# linear_DC_voltage_reg.net
KiCad netlist of a schematic drawn in EAGLE
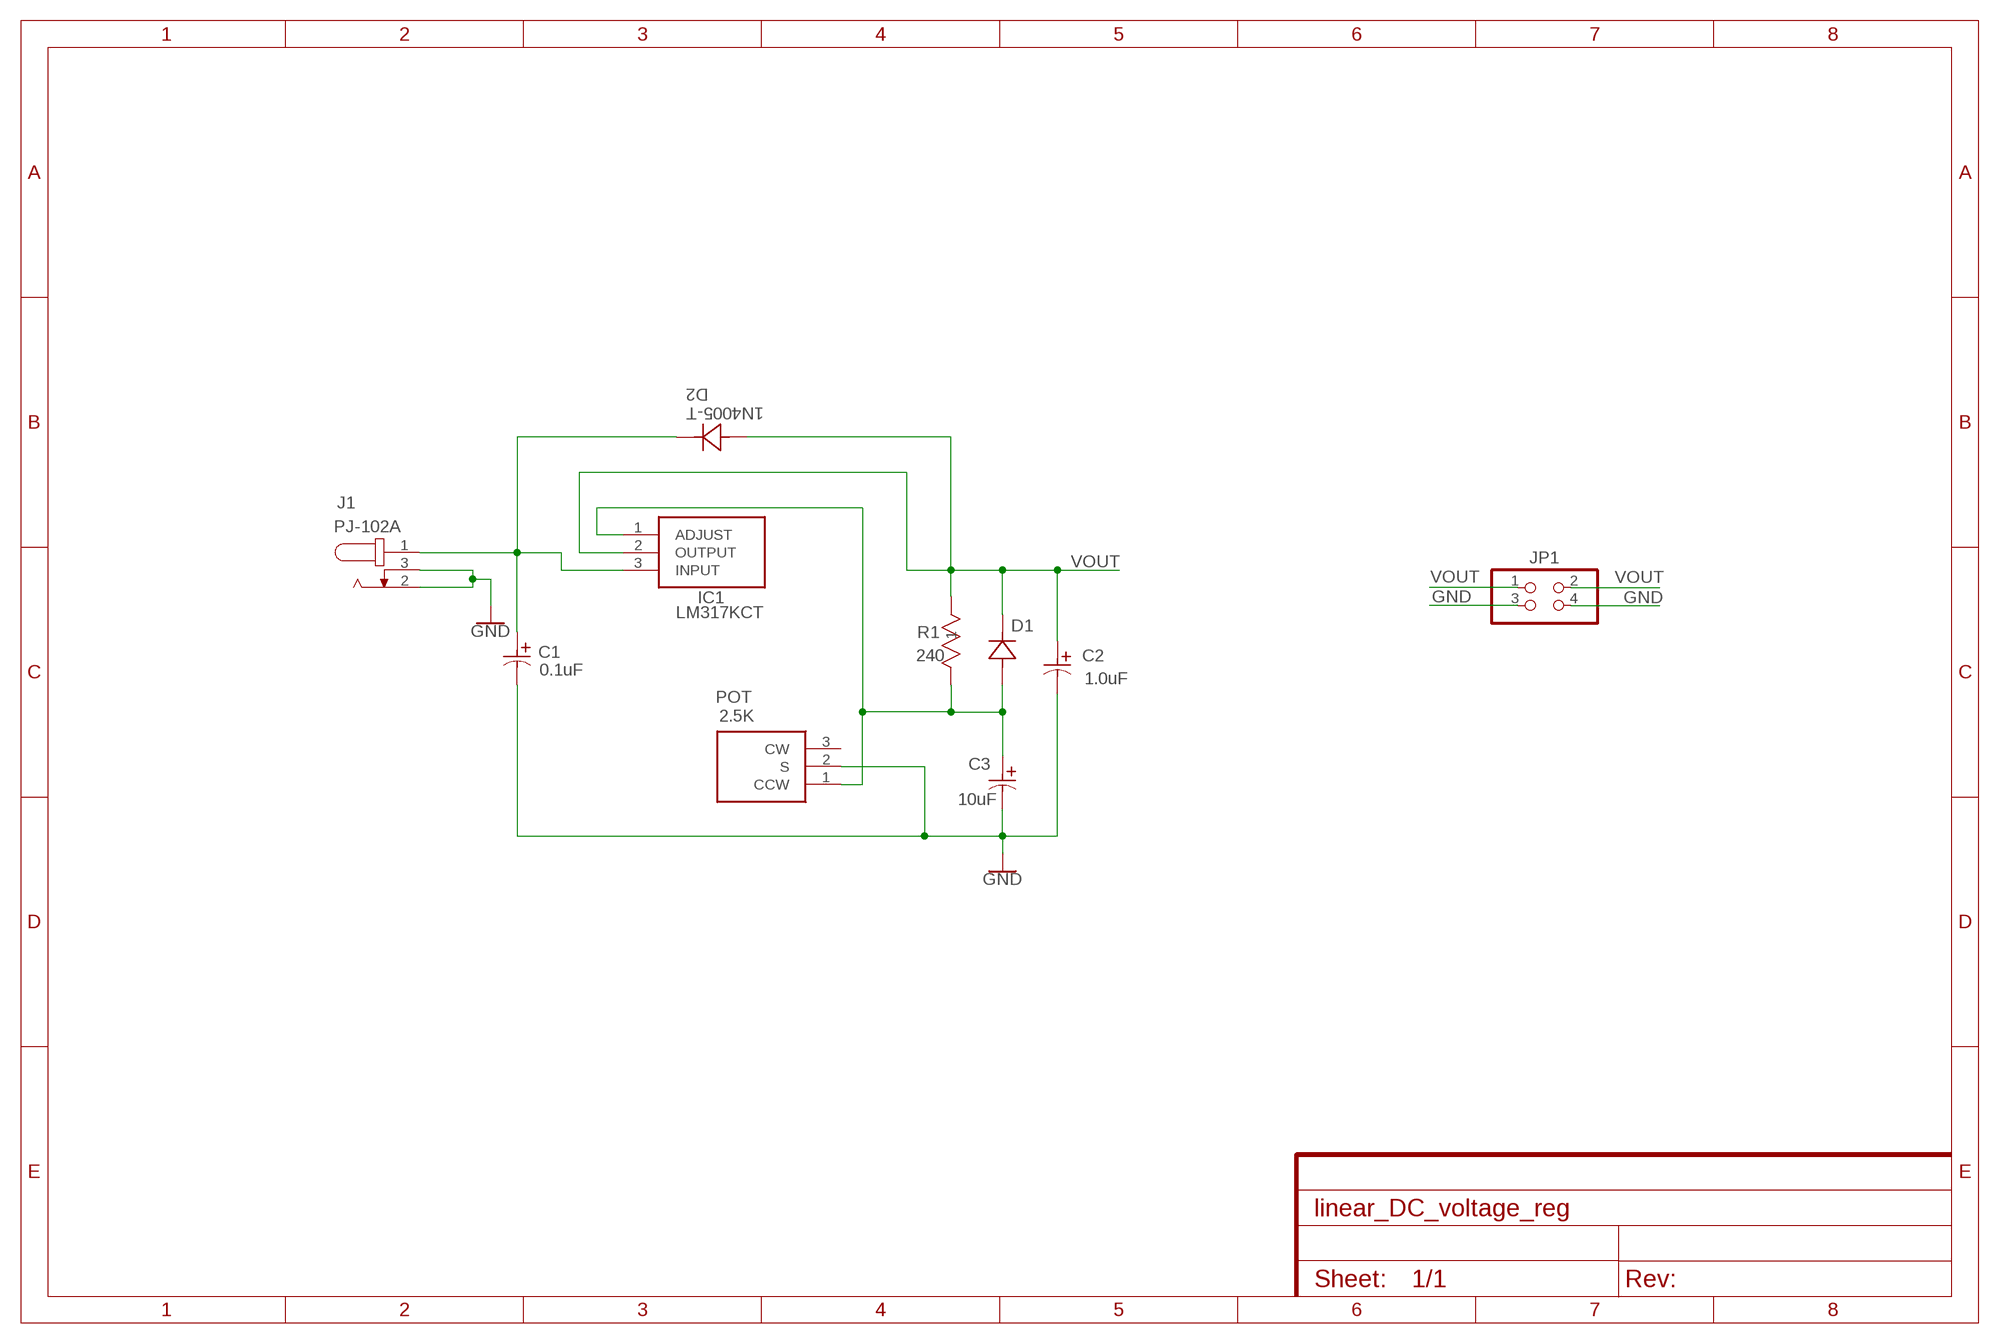
[diagram p0: schematic, sheet 1]

(export (version "E")
  (design (tool "Eeschema 10.0.6"))
  (components
    (comp (ref "C1")
      (value "0.1uF")
      (footprint "eagle-import:CAP_C322_KEM")
      (fields
        (field (name "MANUFACTURER_PART_NUMBER") "C322C104K5R5TA")
        (field (name "COPYRIGHT") "Copyright (C) 2021 Ultra Librarian. All rights reserved.")
      )
      (libsource (lib "eagle-import") (part "C322C104K5R5TA"))
    )
    (comp (ref "C2")
      (value "1.0uF")
      (footprint "eagle-import:CAP_C322_KEM")
      (fields
        (field (name "MANUFACTURER_PART_NUMBER") "C322C104K5R5TA")
        (field (name "COPYRIGHT") "Copyright (C) 2021 Ultra Librarian. All rights reserved.")
      )
      (libsource (lib "eagle-import") (part "C322C104K5R5TA"))
    )
    (comp (ref "C3")
      (value "10uF")
      (footprint "eagle-import:CAP_C322_KEM")
      (fields
        (field (name "MANUFACTURER_PART_NUMBER") "C322C104K5R5TA")
        (field (name "COPYRIGHT") "Copyright (C) 2021 Ultra Librarian. All rights reserved.")
      )
      (libsource (lib "eagle-import") (part "C322C104K5R5TA"))
    )
    (comp (ref "D1")
      (value "1N4005-T")
      (footprint "eagle-import:DO-41_DIO")
      (fields (field (name "COPYRIGHT") "Copyright (C) 2021 Ultra Librarian. All rights reserved."))
      (libsource (lib "eagle-import") (part "1N4005-T"))
    )
    (comp (ref "D2")
      (value "1N4005-T")
      (footprint "eagle-import:DO-41_DIO")
      (fields (field (name "COPYRIGHT") "Copyright (C) 2021 Ultra Librarian. All rights reserved."))
      (libsource (lib "eagle-import") (part "1N4005-T"))
    )
    (comp (ref "IC1")
      (value "LM317KCT")
      (footprint "eagle-import:TO254P465X1016X1883-3P")
      (fields (field (name "MOUSER_PART_NUMBER") "595-LM317KCT"))
      (libsource (lib "eagle-import") (part "LM317KCT"))
    )
    (comp (ref "J1")
      (value "PJ-102A")
      (footprint "eagle-import:CUI_PJ-102A")
      (fields (field (name "DIGI-KEY_PART_NUMBER") "CP-102AH-ND") (field (name "MF") "CUI Devices"))
      (libsource (lib "eagle-import") (part "PJ-102A"))
    )
    (comp (ref "JP1")
      (value "PINHD-2X2")
      (footprint "eagle-import:2X02")
      (libsource (lib "eagle-import") (part "PINHD-2X2"))
    )
    (comp (ref "POT")
      (value "2.5K")
      (footprint "eagle-import:P160KN0FC18C2K5")
      (fields (field (name "MANUFACTURER_PART_NUMBER") "P160KN-0FC18C2K5"))
      (libsource (lib "eagle-import") (part "P160KN-0FC18C2K5"))
    )
    (comp (ref "R1")
      (value "240")
      (footprint "eagle-import:STA_CFM12_STP")
      (fields
        (field (name "MANUFACTURER_PART_NUMBER") "CFM12JT240R")
        (field (name "COPYRIGHT") "Copyright (C) 2021 Ultra Librarian. All rights reserved.")
      )
      (libsource (lib "eagle-import") (part "CFM12JT240R"))
    )
  )
  (nets
    (net (code "1") (name "/VOUT") (class "Default")
      (node (ref "C2") (pin "1") (pinfunction "1_1") (pintype "passive"))
      (node (ref "D1") (pin "1") (pinfunction "1_1") (pintype "passive"))
      (node (ref "D2") (pin "2") (pinfunction "2_2") (pintype "passive"))
      (node (ref "IC1") (pin "2") (pinfunction "OUTPUT_2") (pintype "bidirectional"))
      (node (ref "JP1") (pin "1") (pinfunction "1_1") (pintype "passive"))
      (node (ref "JP1") (pin "2") (pinfunction "2_2") (pintype "passive"))
      (node (ref "R1") (pin "1") (pinfunction "1_1") (pintype "passive"))
    )
    (net (code "2") (name "GND") (class "Default")
      (node (ref "C1") (pin "2") (pinfunction "2_2") (pintype "passive"))
      (node (ref "C2") (pin "2") (pinfunction "2_2") (pintype "passive"))
      (node (ref "C3") (pin "2") (pinfunction "2_2") (pintype "passive"))
      (node (ref "J1") (pin "2") (pinfunction "2_2") (pintype "passive"))
      (node (ref "J1") (pin "3") (pinfunction "3_3") (pintype "passive"))
      (node (ref "JP1") (pin "3") (pinfunction "3_3") (pintype "passive"))
      (node (ref "JP1") (pin "4") (pinfunction "4_4") (pintype "passive"))
      (node (ref "POT") (pin "2") (pinfunction "S_2") (pintype "bidirectional"))
    )
    (net (code "3") (name "Net-(IC1-ADJUST)") (class "Default")
      (node (ref "C3") (pin "1") (pinfunction "1_1") (pintype "passive"))
      (node (ref "D1") (pin "2") (pinfunction "2_2") (pintype "passive"))
      (node (ref "IC1") (pin "1") (pinfunction "ADJUST_1") (pintype "bidirectional"))
      (node (ref "POT") (pin "1") (pinfunction "CCW_1") (pintype "bidirectional"))
      (node (ref "R1") (pin "2") (pinfunction "2_2") (pintype "passive"))
    )
    (net (code "4") (name "Net-(IC1-INPUT)") (class "Default")
      (node (ref "C1") (pin "1") (pinfunction "1_1") (pintype "passive"))
      (node (ref "D2") (pin "1") (pinfunction "1_1") (pintype "passive"))
      (node (ref "IC1") (pin "3") (pinfunction "INPUT_3") (pintype "bidirectional"))
      (node (ref "J1") (pin "1") (pinfunction "1_1") (pintype "passive"))
    )
    (net (code "5") (name "unconnected-(POT-CW-Pad3)") (class "Default")
      (node (ref "POT") (pin "3") (pinfunction "CW_3") (pintype "bidirectional"))
    )
  )
)
